# EPS_Battery_Controller_Current-Meas.net
KiCad netlist of a schematic drawn in Altium Designer
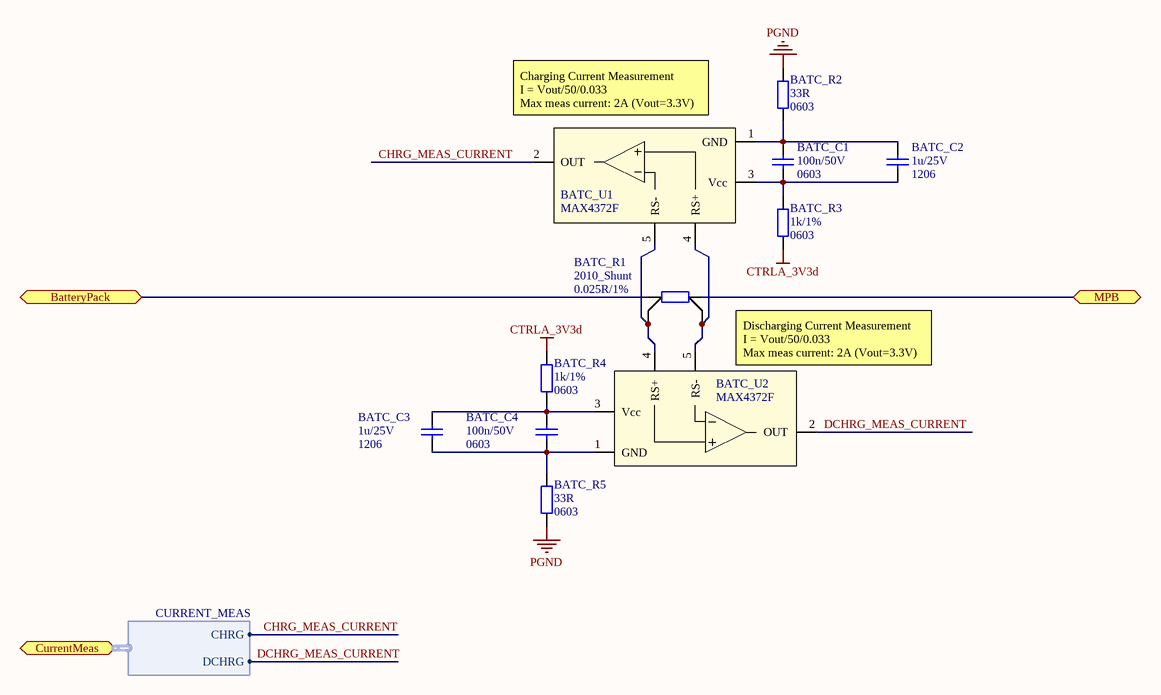
[diagram p0: EPS_Battery_Controller_Current-Meas.SchDoc]

(export (version "E")
  (design (tool "Eeschema 10.0.6"))
  (components
    (comp (ref "BATC_C1")
      (value "100n/50V")
      (footprint "SMD_Capacitor_0603")
      (description "Ceramic Cap Murata Automotive 100n/50V X7R 0603")
      (fields
        (field (name "MANUFACTURER") "Murata")
        (field (name "MANUFACTURERPARTNUMBER") "GCJ188R71H104KA12D")
        (field (name "PACKAGE") "0603")
      )
      (libsource (lib "capacitors") (part "Cer_GCJ188R71H104KA12D"))
    )
    (comp (ref "BATC_C2")
      (value "1u/25V")
      (footprint "SMD_Capacitor_1206")
      (description "Ceramic Cap Kemet COTS 1u/25V X7R 1206")
      (fields
        (field (name "MANUFACTURERPARTNUMBER") "C1206T105K3RALTU")
        (field (name "MANUFACTURER") "Kemet")
        (field (name "PACKAGE") "1206")
      )
      (libsource (lib "capacitors") (part "Cer_C1206T105K3RALTU"))
    )
    (comp (ref "BATC_C3")
      (value "1u/25V")
      (footprint "SMD_Capacitor_1206")
      (description "Ceramic Cap Kemet COTS 1u/25V X7R 1206")
      (fields
        (field (name "MANUFACTURERPARTNUMBER") "C1206T105K3RALTU")
        (field (name "MANUFACTURER") "Kemet")
        (field (name "PACKAGE") "1206")
      )
      (libsource (lib "capacitors") (part "Cer_C1206T105K3RALTU"))
    )
    (comp (ref "BATC_C4")
      (value "100n/50V")
      (footprint "SMD_Capacitor_0603")
      (description "Ceramic Cap Murata Automotive 100n/50V X7R 0603")
      (fields
        (field (name "MANUFACTURER") "Murata")
        (field (name "MANUFACTURERPARTNUMBER") "GCJ188R71H104KA12D")
        (field (name "PACKAGE") "0603")
      )
      (libsource (lib "capacitors") (part "Cer_GCJ188R71H104KA12D"))
    )
    (comp (ref "BATC_R1")
      (value "0.025R/1%")
      (footprint "SMD_Resistor-shunt_2010")
      (description "1W current sensing shunt resistor")
      (fields
        (field (name "MANUFACTURER") "Viking")
        (field (name "MANUFACTURERPARTNUMBER") "CS10FTHTR025")
        (field (name "PACKAGE") "2010_Shunt")
      )
      (libsource (lib "resistors") (part "CS10FTHTR025"))
    )
    (comp (ref "BATC_R2")
      (value "33R")
      (footprint "SMD_Resistor_0603")
      (fields (field (name "PACKAGE") "0603"))
      (libsource (lib "resistors") (part "Res"))
    )
    (comp (ref "BATC_R3")
      (value "1k/1%")
      (footprint "SMD_Resistor_0603")
      (fields (field (name "PACKAGE") "0603"))
      (libsource (lib "resistors") (part "Res"))
    )
    (comp (ref "BATC_R4")
      (value "1k/1%")
      (footprint "SMD_Resistor_0603")
      (fields (field (name "PACKAGE") "0603"))
      (libsource (lib "") (part "Res_1"))
    )
    (comp (ref "BATC_R5")
      (value "33R")
      (footprint "SMD_Resistor_0603")
      (fields (field (name "PACKAGE") "0603"))
      (libsource (lib "resistors") (part "Res"))
    )
    (comp (ref "BATC_U1")
      (value "MAX4372F")
      (footprint "SOT23-5")
      (description "High-Side Current-Sense Amplifier with Voltage Output")
      (fields (field (name "MANUFACTURER") "Maxim Integrated Products"))
      (libsource (lib "microcircuits") (part "MAX4372"))
    )
    (comp (ref "BATC_U2")
      (value "MAX4372F")
      (footprint "SOT23-5")
      (description "High-Side Current-Sense Amplifier with Voltage Output")
      (fields (field (name "MANUFACTURER") "Maxim Integrated Products"))
      (libsource (lib "") (part "MAX4372_1"))
    )
  )
  (nets
    (net (code "2") (name "/BatteryPack") (class "Default")
      (node (ref "BATC_R1") (pin "1") (pinfunction "1_1") (pintype "passive"))
    )
    (net (code "3") (name "/CHRG_MEAS_CURRENT") (class "Default")
      (node (ref "BATC_U1") (pin "2") (pinfunction "OUT_2") (pintype "passive"))
    )
    (net (code "4") (name "/DCHRG_MEAS_CURRENT") (class "Default")
      (node (ref "BATC_U2") (pin "2") (pinfunction "OUT_2") (pintype "passive"))
    )
    (net (code "5") (name "/MPB") (class "Default")
      (node (ref "BATC_R1") (pin "4") (pinfunction "4_4") (pintype "passive"))
    )
    (net (code "7") (name "CTRLA_3V3d") (class "Default")
      (node (ref "BATC_R3") (pin "1") (pinfunction "1_1") (pintype "passive"))
      (node (ref "BATC_R4") (pin "1") (pinfunction "1_1") (pintype "passive"))
    )
    (net (code "8") (name "Net-(BATC_U1-GND)") (class "Default")
      (node (ref "BATC_C1") (pin "1") (pinfunction "1_1") (pintype "passive"))
      (node (ref "BATC_C2") (pin "1") (pinfunction "1_1") (pintype "passive"))
      (node (ref "BATC_R2") (pin "1") (pinfunction "1_1") (pintype "passive"))
      (node (ref "BATC_U1") (pin "1") (pinfunction "GND_1") (pintype "passive"))
    )
    (net (code "9") (name "Net-(BATC_U1-RS+)") (class "Default")
      (node (ref "BATC_R1") (pin "3") (pinfunction "3_3") (pintype "passive"))
      (node (ref "BATC_U1") (pin "4") (pinfunction "RS+_4") (pintype "passive"))
      (node (ref "BATC_U2") (pin "5") (pinfunction "RS-_5") (pintype "passive"))
    )
    (net (code "10") (name "Net-(BATC_U1-RS-)") (class "Default")
      (node (ref "BATC_R1") (pin "2") (pinfunction "2_2") (pintype "passive"))
      (node (ref "BATC_U1") (pin "5") (pinfunction "RS-_5") (pintype "passive"))
      (node (ref "BATC_U2") (pin "4") (pinfunction "RS+_4") (pintype "passive"))
    )
    (net (code "11") (name "Net-(BATC_U1-Vcc)") (class "Default")
      (node (ref "BATC_C1") (pin "2") (pinfunction "2_2") (pintype "passive"))
      (node (ref "BATC_C2") (pin "2") (pinfunction "2_2") (pintype "passive"))
      (node (ref "BATC_R3") (pin "2") (pinfunction "2_2") (pintype "passive"))
      (node (ref "BATC_U1") (pin "3") (pinfunction "Vcc_3") (pintype "passive"))
    )
    (net (code "12") (name "Net-(BATC_U2-GND)") (class "Default")
      (node (ref "BATC_C3") (pin "2") (pinfunction "2_2") (pintype "passive"))
      (node (ref "BATC_C4") (pin "2") (pinfunction "2_2") (pintype "passive"))
      (node (ref "BATC_R5") (pin "2") (pinfunction "2_2") (pintype "passive"))
      (node (ref "BATC_U2") (pin "1") (pinfunction "GND_1") (pintype "passive"))
    )
    (net (code "13") (name "Net-(BATC_U2-Vcc)") (class "Default")
      (node (ref "BATC_C3") (pin "1") (pinfunction "1_1") (pintype "passive"))
      (node (ref "BATC_C4") (pin "1") (pinfunction "1_1") (pintype "passive"))
      (node (ref "BATC_R4") (pin "2") (pinfunction "2_2") (pintype "passive"))
      (node (ref "BATC_U2") (pin "3") (pinfunction "Vcc_3") (pintype "passive"))
    )
    (net (code "14") (name "PGND") (class "Default")
      (node (ref "BATC_R2") (pin "2") (pinfunction "2_2") (pintype "passive"))
      (node (ref "BATC_R5") (pin "1") (pinfunction "1_1") (pintype "passive"))
    )
  )
)
